# BUZZER_RELAY.net
KiCad netlist of a schematic drawn in Altium Designer
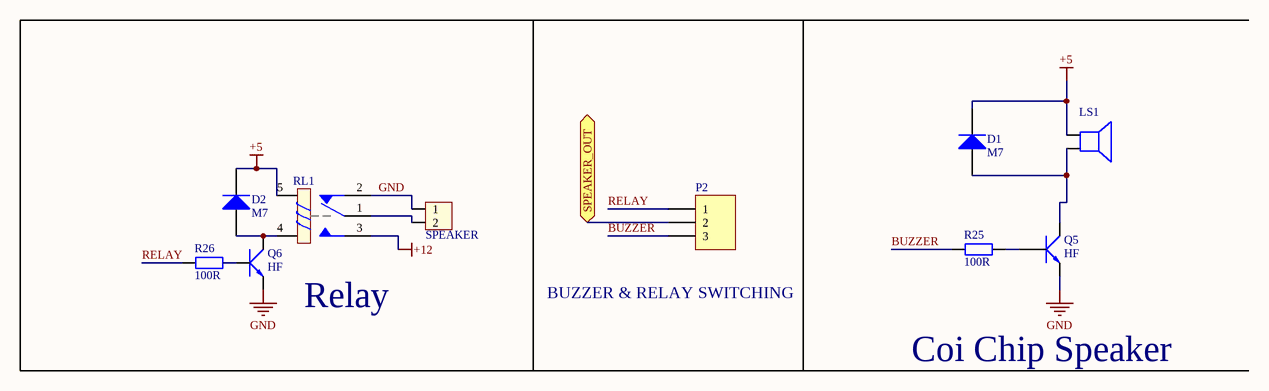
[diagram p0: BUZZER_RELAY.SchDoc]

(export (version "E")
  (design (tool "Eeschema 10.0.6"))
  (components
    (comp (ref "D1")
      (value "M7")
      (footprint "DIODE SMA")
      (description "Dán")
      (libsource (lib "Altium_Lib_by_KhueNguyenCreator") (part "Diode M7 ( 4007 )"))
    )
    (comp (ref "D2")
      (value "M7")
      (footprint "DIODE SMA")
      (description "Dán")
      (libsource (lib "Altium_Lib_by_KhueNguyenCreator") (part "Diode M7 ( 4007 )"))
    )
    (comp (ref "H1")
      (value "SPEAKER")
      (footprint "XH2.54M-2")
      (description "Cắm")
      (libsource (lib "Altium_Lib_by_KhueNguyenCreator") (part "Header 2P 2.54 Duc Thang"))
    )
    (comp (ref "LS1")
      (value "Coi Chip Speaker")
      (footprint "Coi Chip Speacker")
      (description "Còi chip")
      (libsource (lib "Altium_Lib_by_KhueNguyenCreator") (part "Coi Chip Speaker"))
    )
    (comp (ref "P2")
      (value "BUZZER & RELAY SWITCHING")
      (footprint "HDR1X3")
      (description "Header, 3-Pin")
      (fields (field (name "PUBLISHER") "Altium Limited"))
      (libsource (lib "Miscellaneous Connectors") (part "Header 3"))
    )
    (comp (ref "Q5")
      (value "HF")
      (footprint "SOT23")
      (description "NPN transistor")
      (libsource (lib "Altium_Lib_by_KhueNguyenCreator") (part "C1815 HF SMD"))
    )
    (comp (ref "Q6")
      (value "HF")
      (footprint "SOT23")
      (description "NPN transistor")
      (libsource (lib "Altium_Lib_by_KhueNguyenCreator") (part "C1815 HF SMD"))
    )
    (comp (ref "R25")
      (value "100R")
      (footprint "tro smd 0603")
      (description "Dán")
      (libsource (lib "Altium_Lib_by_KhueNguyenCreator") (part "Tro 0603 5% 100R"))
    )
    (comp (ref "R26")
      (value "100R")
      (footprint "tro smd 0603")
      (description "Dán")
      (libsource (lib "Altium_Lib_by_KhueNguyenCreator") (part "Tro 0603 5% 100R"))
    )
    (comp (ref "RL1")
      (value "Relay")
      (footprint "Relay 5 Chan SRD")
      (description "Relay 5 Chan")
      (libsource (lib "Altium_Lib_by_KhueNguyenCreator") (part "Relay 5 Chan SRD"))
    )
  )
  (nets
    (net (code "1") (name "+5") (class "Default")
      (node (ref "D1") (pin "2") (pinfunction "K_2") (pintype "passive"))
      (node (ref "D2") (pin "2") (pinfunction "K_2") (pintype "passive"))
      (node (ref "LS1") (pin "1") (pinfunction "1_1") (pintype "passive"))
      (node (ref "RL1") (pin "5") (pinfunction "5_5") (pintype "passive"))
    )
    (net (code "2") (name "+12") (class "Default")
      (node (ref "RL1") (pin "3") (pinfunction "3_3") (pintype "passive"))
    )
    (net (code "3") (name "/BUZZER") (class "Default")
      (node (ref "P2") (pin "3") (pinfunction "3_3") (pintype "passive"))
      (node (ref "R25") (pin "1") (pinfunction "1_1") (pintype "passive"))
    )
    (net (code "4") (name "/RELAY") (class "Default")
      (node (ref "P2") (pin "1") (pinfunction "1_1") (pintype "passive"))
      (node (ref "R26") (pin "1") (pinfunction "1_1") (pintype "passive"))
    )
    (net (code "5") (name "/SPEAKER_OUT") (class "Default")
      (node (ref "P2") (pin "2") (pinfunction "2_2") (pintype "passive"))
    )
    (net (code "6") (name "GND") (class "Default")
      (node (ref "H1") (pin "1") (pinfunction "1_1") (pintype "passive"))
      (node (ref "Q5") (pin "2") (pinfunction "E_2") (pintype "passive"))
      (node (ref "Q6") (pin "2") (pinfunction "E_2") (pintype "passive"))
      (node (ref "RL1") (pin "2") (pinfunction "2_2") (pintype "passive"))
    )
    (net (code "7") (name "Net-(D1-A)") (class "Default")
      (node (ref "D1") (pin "1") (pinfunction "A_1") (pintype "passive"))
      (node (ref "LS1") (pin "2") (pinfunction "2_2") (pintype "passive"))
      (node (ref "Q5") (pin "3") (pinfunction "C_3") (pintype "passive"))
    )
    (net (code "8") (name "Net-(D2-A)") (class "Default")
      (node (ref "D2") (pin "1") (pinfunction "A_1") (pintype "passive"))
      (node (ref "Q6") (pin "3") (pinfunction "C_3") (pintype "passive"))
      (node (ref "RL1") (pin "4") (pinfunction "4_4") (pintype "passive"))
    )
    (net (code "9") (name "Net-(H1-Pad2)") (class "Default")
      (node (ref "H1") (pin "2") (pinfunction "2_2") (pintype "passive"))
      (node (ref "RL1") (pin "1") (pinfunction "1_1") (pintype "passive"))
    )
    (net (code "10") (name "Net-(Q5-B)") (class "Default")
      (node (ref "Q5") (pin "1") (pinfunction "B_1") (pintype "passive"))
      (node (ref "R25") (pin "2") (pinfunction "2_2") (pintype "passive"))
    )
    (net (code "11") (name "Net-(Q6-B)") (class "Default")
      (node (ref "Q6") (pin "1") (pinfunction "B_1") (pintype "passive"))
      (node (ref "R26") (pin "2") (pinfunction "2_2") (pintype "passive"))
    )
  )
)
